# Drury-DABSC.net
KiCad netlist of a schematic drawn in EAGLE
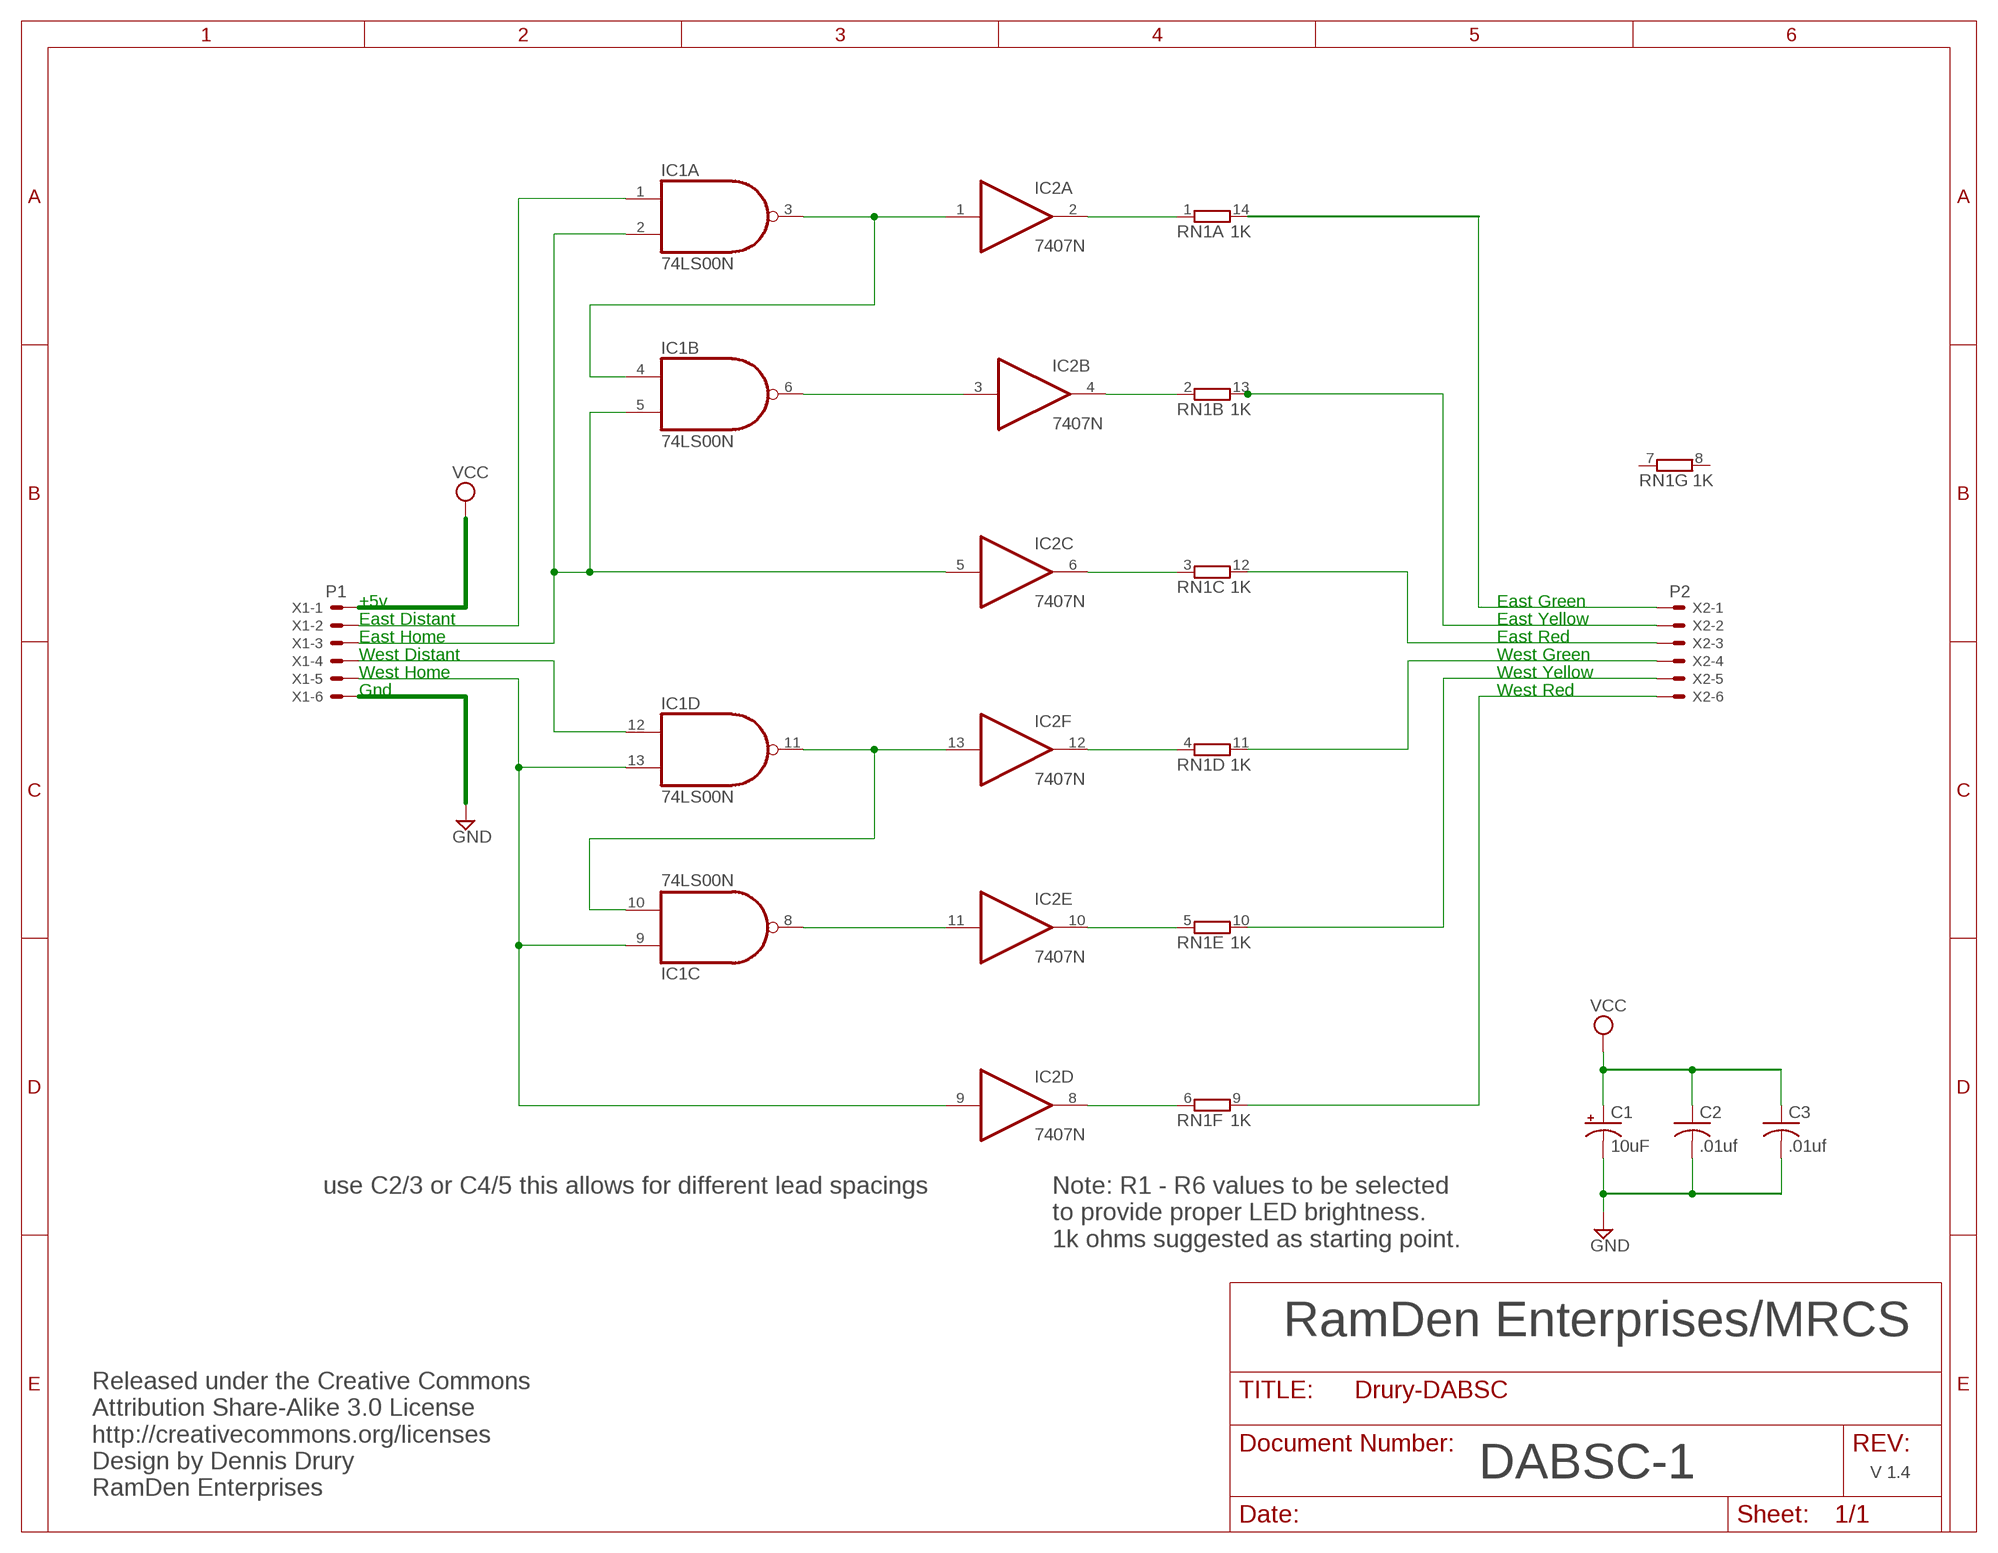
[diagram p0: schematic, sheet 1]

(export (version "E")
  (design (tool "Eeschema 10.0.6"))
  (components
    (comp (ref "C1")
      (value "10uF")
      (footprint "eagle-import:E2-5")
      (libsource (lib "eagle-import") (part "CAP-POLPTH-2MM"))
    )
    (comp (ref "C2")
      (value ".01uf")
      (footprint "eagle-import:C050-025X075")
      (libsource (lib "eagle-import") (part "C-US050-025X075"))
    )
    (comp (ref "C3")
      (value ".01uf")
      (footprint "eagle-import:C050-025X075")
      (libsource (lib "eagle-import") (part "C-US050-025X075"))
    )
    (comp (ref "IC1")
      (value "74LS00N")
      (footprint "eagle-import:DIL14")
      (libsource (lib "eagle-import") (part "7400NLS"))
    )
    (comp (ref "IC2")
      (value "7407N")
      (footprint "eagle-import:DIL14")
      (libsource (lib "eagle-import") (part "7407N"))
    )
    (comp (ref "RN1")
      (value "1K")
      (footprint "eagle-import:DIL14")
      (libsource (lib "eagle-import") (part "7R-N"))
    )
    (comp (ref "X1")
      (value "P1")
      (footprint "eagle-import:22-23-2061")
      (fields (field (name "MF") "MOLEX") (field (name "MPN") "22-23-2061"))
      (libsource (lib "eagle-import") (part "22-23-2061"))
    )
    (comp (ref "X2")
      (value "P2")
      (footprint "eagle-import:22-23-2061")
      (fields (field (name "MF") "MOLEX") (field (name "MPN") "22-23-2061"))
      (libsource (lib "eagle-import") (part "22-23-2061"))
    )
  )
  (nets
    (net (code "1") (name "GND") (class "Default")
      (node (ref "C1") (pin "-") (pinfunction "-_-") (pintype "passive"))
      (node (ref "C2") (pin "2") (pinfunction "2_2") (pintype "passive"))
      (node (ref "C3") (pin "2") (pinfunction "2_2") (pintype "passive"))
      (node (ref "X1") (pin "6") (pinfunction "S_6") (pintype "passive"))
    )
    (net (code "2") (name "Net-(IC1A-I0)") (class "Default")
      (node (ref "IC1") (pin "1") (pinfunction "I0_1") (pintype "input"))
      (node (ref "X1") (pin "2") (pinfunction "S_2") (pintype "passive"))
    )
    (net (code "3") (name "Net-(IC1A-I1)") (class "Default")
      (node (ref "IC1") (pin "2") (pinfunction "I1_2") (pintype "input"))
      (node (ref "IC1") (pin "5") (pinfunction "I1_5") (pintype "input"))
      (node (ref "IC2") (pin "5") (pinfunction "I_5") (pintype "input"))
      (node (ref "X1") (pin "3") (pinfunction "S_3") (pintype "passive"))
    )
    (net (code "4") (name "Net-(IC1A-O)") (class "Default")
      (node (ref "IC1") (pin "3") (pinfunction "O_3") (pintype "output"))
      (node (ref "IC1") (pin "4") (pinfunction "I0_4") (pintype "input"))
      (node (ref "IC2") (pin "1") (pinfunction "I_1") (pintype "input"))
    )
    (net (code "5") (name "Net-(IC1B-O)") (class "Default")
      (node (ref "IC1") (pin "6") (pinfunction "O_6") (pintype "output"))
      (node (ref "IC2") (pin "3") (pinfunction "I_3") (pintype "input"))
    )
    (net (code "6") (name "Net-(IC1C-I0)") (class "Default")
      (node (ref "IC1") (pin "13") (pinfunction "I1_13") (pintype "input"))
      (node (ref "IC1") (pin "9") (pinfunction "I0_9") (pintype "input"))
      (node (ref "IC2") (pin "9") (pinfunction "I_9") (pintype "input"))
      (node (ref "X1") (pin "5") (pinfunction "S_5") (pintype "passive"))
    )
    (net (code "7") (name "Net-(IC1C-I1)") (class "Default")
      (node (ref "IC1") (pin "10") (pinfunction "I1_10") (pintype "input"))
      (node (ref "IC1") (pin "11") (pinfunction "O_11") (pintype "output"))
      (node (ref "IC2") (pin "13") (pinfunction "I_13") (pintype "input"))
    )
    (net (code "8") (name "Net-(IC1C-O)") (class "Default")
      (node (ref "IC1") (pin "8") (pinfunction "O_8") (pintype "output"))
      (node (ref "IC2") (pin "11") (pinfunction "I_11") (pintype "input"))
    )
    (net (code "9") (name "Net-(IC1D-I0)") (class "Default")
      (node (ref "IC1") (pin "12") (pinfunction "I0_12") (pintype "input"))
      (node (ref "X1") (pin "4") (pinfunction "S_4") (pintype "passive"))
    )
    (net (code "10") (name "Net-(IC2A-O)") (class "Default")
      (node (ref "IC2") (pin "2") (pinfunction "O_2") (pintype "open_collector"))
      (node (ref "RN1") (pin "1") (pinfunction "1_1") (pintype "passive"))
    )
    (net (code "11") (name "Net-(IC2B-O)") (class "Default")
      (node (ref "IC2") (pin "4") (pinfunction "O_4") (pintype "open_collector"))
      (node (ref "RN1") (pin "2") (pinfunction "1_2") (pintype "passive"))
    )
    (net (code "12") (name "Net-(IC2C-O)") (class "Default")
      (node (ref "IC2") (pin "6") (pinfunction "O_6") (pintype "open_collector"))
      (node (ref "RN1") (pin "3") (pinfunction "1_3") (pintype "passive"))
    )
    (net (code "13") (name "Net-(IC2D-O)") (class "Default")
      (node (ref "IC2") (pin "8") (pinfunction "O_8") (pintype "open_collector"))
      (node (ref "RN1") (pin "6") (pinfunction "1_6") (pintype "passive"))
    )
    (net (code "14") (name "Net-(IC2E-O)") (class "Default")
      (node (ref "IC2") (pin "10") (pinfunction "O_10") (pintype "open_collector"))
      (node (ref "RN1") (pin "5") (pinfunction "1_5") (pintype "passive"))
    )
    (net (code "15") (name "Net-(IC2F-O)") (class "Default")
      (node (ref "IC2") (pin "12") (pinfunction "O_12") (pintype "open_collector"))
      (node (ref "RN1") (pin "4") (pinfunction "1_4") (pintype "passive"))
    )
    (net (code "16") (name "Net-(RN1A-2)") (class "Default")
      (node (ref "RN1") (pin "14") (pinfunction "2_14") (pintype "passive"))
      (node (ref "X2") (pin "1") (pinfunction "S_1") (pintype "passive"))
    )
    (net (code "17") (name "Net-(RN1B-2)") (class "Default")
      (node (ref "RN1") (pin "13") (pinfunction "2_13") (pintype "passive"))
      (node (ref "X2") (pin "2") (pinfunction "S_2") (pintype "passive"))
    )
    (net (code "18") (name "Net-(RN1C-2)") (class "Default")
      (node (ref "RN1") (pin "12") (pinfunction "2_12") (pintype "passive"))
      (node (ref "X2") (pin "3") (pinfunction "S_3") (pintype "passive"))
    )
    (net (code "19") (name "Net-(RN1D-2)") (class "Default")
      (node (ref "RN1") (pin "11") (pinfunction "2_11") (pintype "passive"))
      (node (ref "X2") (pin "4") (pinfunction "S_4") (pintype "passive"))
    )
    (net (code "20") (name "Net-(RN1E-2)") (class "Default")
      (node (ref "RN1") (pin "10") (pinfunction "2_10") (pintype "passive"))
      (node (ref "X2") (pin "5") (pinfunction "S_5") (pintype "passive"))
    )
    (net (code "21") (name "Net-(RN1F-2)") (class "Default")
      (node (ref "RN1") (pin "9") (pinfunction "2_9") (pintype "passive"))
      (node (ref "X2") (pin "6") (pinfunction "S_6") (pintype "passive"))
    )
    (net (code "22") (name "VCC") (class "Default")
      (node (ref "C1") (pin "+") (pinfunction "+_+") (pintype "passive"))
      (node (ref "C2") (pin "1") (pinfunction "1_1") (pintype "passive"))
      (node (ref "C3") (pin "1") (pinfunction "1_1") (pintype "passive"))
      (node (ref "X1") (pin "1") (pinfunction "S_1") (pintype "passive"))
    )
    (net (code "23") (name "unconnected-(RN1G-1-Pad7)") (class "Default")
      (node (ref "RN1") (pin "7") (pinfunction "1_7") (pintype "passive"))
    )
    (net (code "24") (name "unconnected-(RN1G-2-Pad8)") (class "Default")
      (node (ref "RN1") (pin "8") (pinfunction "2_8") (pintype "passive"))
    )
  )
)
